# PDB_Protection.net
KiCad netlist of a schematic drawn in Altium Designer
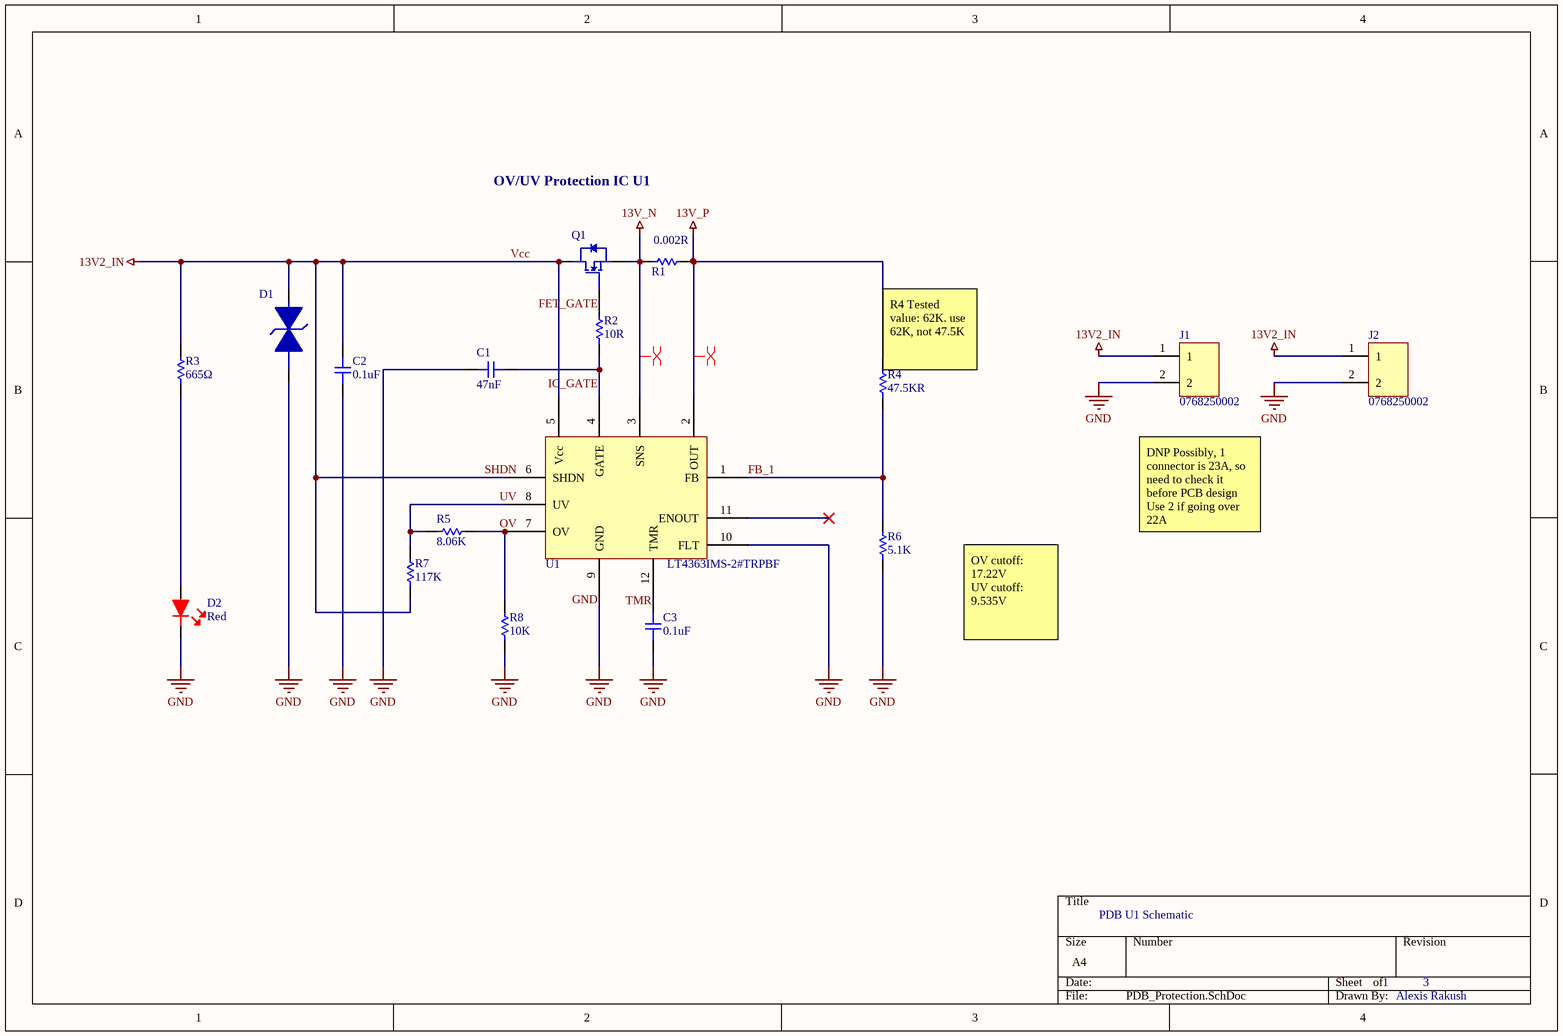
[diagram p0: PDB_Protection.SchDoc]

(export (version "E")
  (design (tool "Eeschema 10.0.6"))
  (components
    (comp (ref "C1")
      (value "47nF")
      (footprint "CAP-0603")
      (description "CAP CER 0.047UF 50V X7R 0603")
      (fields
        (field (name "MANUFACTURER") "Yageo")
        (field (name "MANUFACTURER PART NUMBER") "CC0603KRX7R9BB473")
      )
      (libsource (lib "Capacitors") (part "0603-47nF-50V"))
    )
    (comp (ref "C2")
      (value "0.1uF")
      (footprint "CAP-0805")
      (description "CAP CER 0.1UF 50V Y5V 0805")
      (fields
        (field (name "MANUFACTURER") "KEMET")
        (field (name "MANUFACTURER PART NUMBER") "C0805C104Z5VACTU")
      )
      (libsource (lib "Capacitors") (part "0805-0.1uF-50V"))
    )
    (comp (ref "C3")
      (value "0.1uF")
      (footprint "CAP-0603")
      (description "CAP CER 0.1UF 16V X7R 0603")
      (fields
        (field (name "MANUFACTURER") "KEMET")
        (field (name "MANUFACTURER PART NUMBER") "C0603C104M4RACTU")
      )
      (libsource (lib "PDB_sch_lib") (part "0603-0.1uF-16V"))
    )
    (comp (ref "D1")
      (value "TVS DIODE")
      (footprint "DIOM4326X24N")
      (description "TVS DIODE 58VWM 93.6VC SMA")
      (fields (field (name "MANUFACTURER") "Diodes") (field (name "MANUFACTURER PART NUMBER") "SMAJ58A-13-F"))
      (libsource (lib "PDB_sch_lib") (part "SMAJ58A-13-F"))
    )
    (comp (ref "D2")
      (value "Red")
      (footprint "LED-0603")
      (description "LED RED CLEAR 0603 SMD")
      (fields
        (field (name "MANUFACTURER") "Wurth Electronics")
        (field (name "MANUFACTURER PART NUMBER") "150060RS75000")
      )
      (libsource (lib "PDB_sch_lib") (part "LED-Red"))
    )
    (comp (ref "J1")
      (value "0768250002")
      (footprint "2X1PIN")
      (description "CONN HEADER R/A 2POS")
      (fields (field (name "MANUFACTURER") "Molex") (field (name "MANUFACTURER PART NUMBER") "76825-0002"))
      (libsource (lib "PDB_sch_lib") (part "2X1PIN"))
    )
    (comp (ref "J2")
      (value "0768250002")
      (footprint "2X1PIN")
      (description "CONN HEADER R/A 2POS")
      (fields (field (name "MANUFACTURER") "Molex") (field (name "MANUFACTURER PART NUMBER") "76825-0002"))
      (libsource (lib "PDB_sch_lib") (part "2X1PIN"))
    )
    (comp (ref "Q1")
      (value "FDB33N25TM")
      (footprint "DPAK254P1524X483-3N")
      (description "Trans MOSFET N-CH 250V 33A 3-Pin(2+Tab) D2PAK T/R")
      (fields (field (name "MANUFACTURER") "ON Semiconductor / Fairchild"))
      (libsource (lib "PDB_sch_lib") (part "FDB33N25TM"))
    )
    (comp (ref "R1")
      (value "0.002R")
      (footprint "RES-2512")
      (fields
        (field (name "MANUFACTURER") "Bourns")
        (field (name "MANUFACTURER PART NUMBER") "CSS2H-2512K-2L00F")
        (field (name "TOLERANCE") "1%")
      )
      (libsource (lib "Resistors") (part "2512-0.002R-5W"))
    )
    (comp (ref "R2")
      (value "10R")
      (footprint "RES-0603")
      (description "RES SMD 10 OHM 1% 1/10W 0603")
      (fields
        (field (name "MANUFACTURER") "Yageo")
        (field (name "MANUFACTURER PART NUMBER") "RC0805FR-0710RL")
      )
      (libsource (lib "PDB_sch_lib") (part "0603-10R"))
    )
    (comp (ref "R3")
      (value "665Ω")
      (footprint "RES-0603")
      (description "RES SMD 665 OHM 1% 1/10W 0603")
      (fields
        (field (name "MANUFACTURER") "Yageo")
        (field (name "MANUFACTURER PART NUMBER") "RC0603FR-07665RL")
      )
      (libsource (lib "Resistors") (part "0603-665R"))
    )
    (comp (ref "R4")
      (value "47.5KR")
      (footprint "RES-0603")
      (description "RES SMD 47.5K OHM 1% 1/10W 0603")
      (fields
        (field (name "MANUFACTURER") "Vishay")
        (field (name "MANUFACTURER PART NUMBER") "CRCW080547K5FKEA")
      )
      (libsource (lib "PDB_sch_lib") (part "0603-47.5KR"))
    )
    (comp (ref "R5")
      (value "8.06K")
      (footprint "RES-0603")
      (description "RES SMD 8.06K OHM 1% 1/10W 0603")
      (fields
        (field (name "MANUFACTURER") "Panasonic")
        (field (name "MANUFACTURER PART NUMBER") "ERJ-3EKF8061V")
      )
      (libsource (lib "PDB_sch_lib") (part "0603-8.06KR"))
    )
    (comp (ref "R6")
      (value "5.1K")
      (footprint "RES-0805")
      (description "RES SMD 5.1K OHM 1% 1/8W 0805")
      (fields
        (field (name "MANUFACTURER") "TE Connectivity")
        (field (name "MANUFACTURER PART NUMBER") "1623257-1")
      )
      (libsource (lib "PDB_sch_lib") (part "0805-5.1KR"))
    )
    (comp (ref "R7")
      (value "117K")
      (footprint "RES-0603")
      (description "RES 117K OHM 0.5% 1/10W 0603")
      (fields
        (field (name "MANUFACTURER") "Yageo")
        (field (name "MANUFACTURER PART NUMBER") "RT0603DRE07117KL")
      )
      (libsource (lib "PDB_sch_lib") (part "0603-117KR"))
    )
    (comp (ref "R8")
      (value "10K")
      (footprint "RES-0603")
      (description "RES 10K OHM 1% 1/10W 0603")
      (fields
        (field (name "MANUFACTURER") "Yageo")
        (field (name "MANUFACTURER PART NUMBER") "RC0805FR-0710KL")
      )
      (libsource (lib "PDB_sch_lib") (part "0603-10KR"))
    )
    (comp (ref "U1")
      (value "LT4363IMS-2#TRPBF")
      (footprint "MSOP-12")
      (description "IC SURGE STOPPER HV 12-MSOP")
      (fields (field (name "MANUFACTURER") "Analog Devices / Linear Technology"))
      (libsource (lib "PDB_sch_lib") (part "LT4363IMS-2#TRPBF"))
    )
  )
  (nets
    (net (code "1") (name "/FB_1") (class "Default")
      (node (ref "R4") (pin "1") (pinfunction "1_1") (pintype "passive"))
      (node (ref "R6") (pin "2") (pinfunction "2_2") (pintype "passive"))
      (node (ref "U1") (pin "1") (pinfunction "FB_1") (pintype "passive"))
    )
    (net (code "2") (name "/FET_GATE") (class "Default")
      (node (ref "Q1") (pin "1") (pinfunction "1_1") (pintype "passive"))
      (node (ref "R2") (pin "2") (pinfunction "2_2") (pintype "passive"))
    )
    (net (code "3") (name "/IC_GATE") (class "Default")
      (node (ref "C1") (pin "2") (pinfunction "2_2") (pintype "passive"))
      (node (ref "R2") (pin "1") (pinfunction "1_1") (pintype "passive"))
      (node (ref "U1") (pin "4") (pinfunction "GATE_4") (pintype "passive"))
    )
    (net (code "6") (name "/TMR") (class "Default")
      (node (ref "C3") (pin "2") (pinfunction "2_2") (pintype "passive"))
      (node (ref "U1") (pin "12") (pinfunction "TMR_12") (pintype "passive"))
    )
    (net (code "8") (name "13V2_IN") (class "Default")
      (node (ref "C2") (pin "2") (pinfunction "2_2") (pintype "passive"))
      (node (ref "D1") (pin "1") (pinfunction "1_1") (pintype "passive"))
      (node (ref "J1") (pin "1") (pinfunction "1_1") (pintype "passive"))
      (node (ref "J2") (pin "1") (pinfunction "1_1") (pintype "passive"))
      (node (ref "Q1") (pin "4") (pinfunction "4_4") (pintype "passive"))
      (node (ref "R3") (pin "2") (pinfunction "2_2") (pintype "passive"))
      (node (ref "R7") (pin "1") (pinfunction "1_1") (pintype "passive"))
      (node (ref "U1") (pin "5") (pinfunction "Vcc_5") (pintype "passive"))
      (node (ref "U1") (pin "6") (pinfunction "SHDN_6") (pintype "passive"))
    )
    (net (code "9") (name "13V_N") (class "Default")
      (node (ref "Q1") (pin "3") (pinfunction "3_3") (pintype "passive"))
      (node (ref "R1") (pin "1") (pinfunction "1_1") (pintype "passive"))
      (node (ref "U1") (pin "3") (pinfunction "SNS_3") (pintype "passive"))
    )
    (net (code "10") (name "13V_P") (class "Default")
      (node (ref "R1") (pin "2") (pinfunction "2_2") (pintype "passive"))
      (node (ref "R4") (pin "2") (pinfunction "2_2") (pintype "passive"))
      (node (ref "U1") (pin "2") (pinfunction "OUT_2") (pintype "passive"))
    )
    (net (code "11") (name "GND") (class "Default")
      (node (ref "C1") (pin "1") (pinfunction "1_1") (pintype "passive"))
      (node (ref "C2") (pin "1") (pinfunction "1_1") (pintype "passive"))
      (node (ref "C3") (pin "1") (pinfunction "1_1") (pintype "passive"))
      (node (ref "D1") (pin "2") (pinfunction "2_2") (pintype "passive"))
      (node (ref "D2") (pin "2") (pinfunction "2_2") (pintype "passive"))
      (node (ref "J1") (pin "2") (pinfunction "2_2") (pintype "passive"))
      (node (ref "J2") (pin "2") (pinfunction "2_2") (pintype "passive"))
      (node (ref "R6") (pin "1") (pinfunction "1_1") (pintype "passive"))
      (node (ref "R8") (pin "1") (pinfunction "1_1") (pintype "passive"))
      (node (ref "U1") (pin "10") (pinfunction "FLT_10") (pintype "passive"))
      (node (ref "U1") (pin "9") (pinfunction "GND_9") (pintype "passive"))
    )
    (net (code "12") (name "Net-(D2-Pad1)") (class "Default")
      (node (ref "D2") (pin "1") (pinfunction "1_1") (pintype "passive"))
      (node (ref "R3") (pin "1") (pinfunction "1_1") (pintype "passive"))
    )
    (net (code "13") (name "Net-(U1-OV)") (class "Default")
      (node (ref "R5") (pin "2") (pinfunction "2_2") (pintype "passive"))
      (node (ref "R8") (pin "2") (pinfunction "2_2") (pintype "passive"))
      (node (ref "U1") (pin "7") (pinfunction "OV_7") (pintype "passive"))
    )
    (net (code "14") (name "Net-(U1-UV)") (class "Default")
      (node (ref "R5") (pin "1") (pinfunction "1_1") (pintype "passive"))
      (node (ref "R7") (pin "2") (pinfunction "2_2") (pintype "passive"))
      (node (ref "U1") (pin "8") (pinfunction "UV_8") (pintype "passive"))
    )
    (net (code "15") (name "unconnected-(U1-ENOUT-Pad11)") (class "Default")
      (node (ref "U1") (pin "11") (pinfunction "ENOUT_11") (pintype "passive+no_connect"))
    )
  )
)
